# ESP32_CUSTOM.net
KiCad netlist of a schematic drawn in Altium Designer
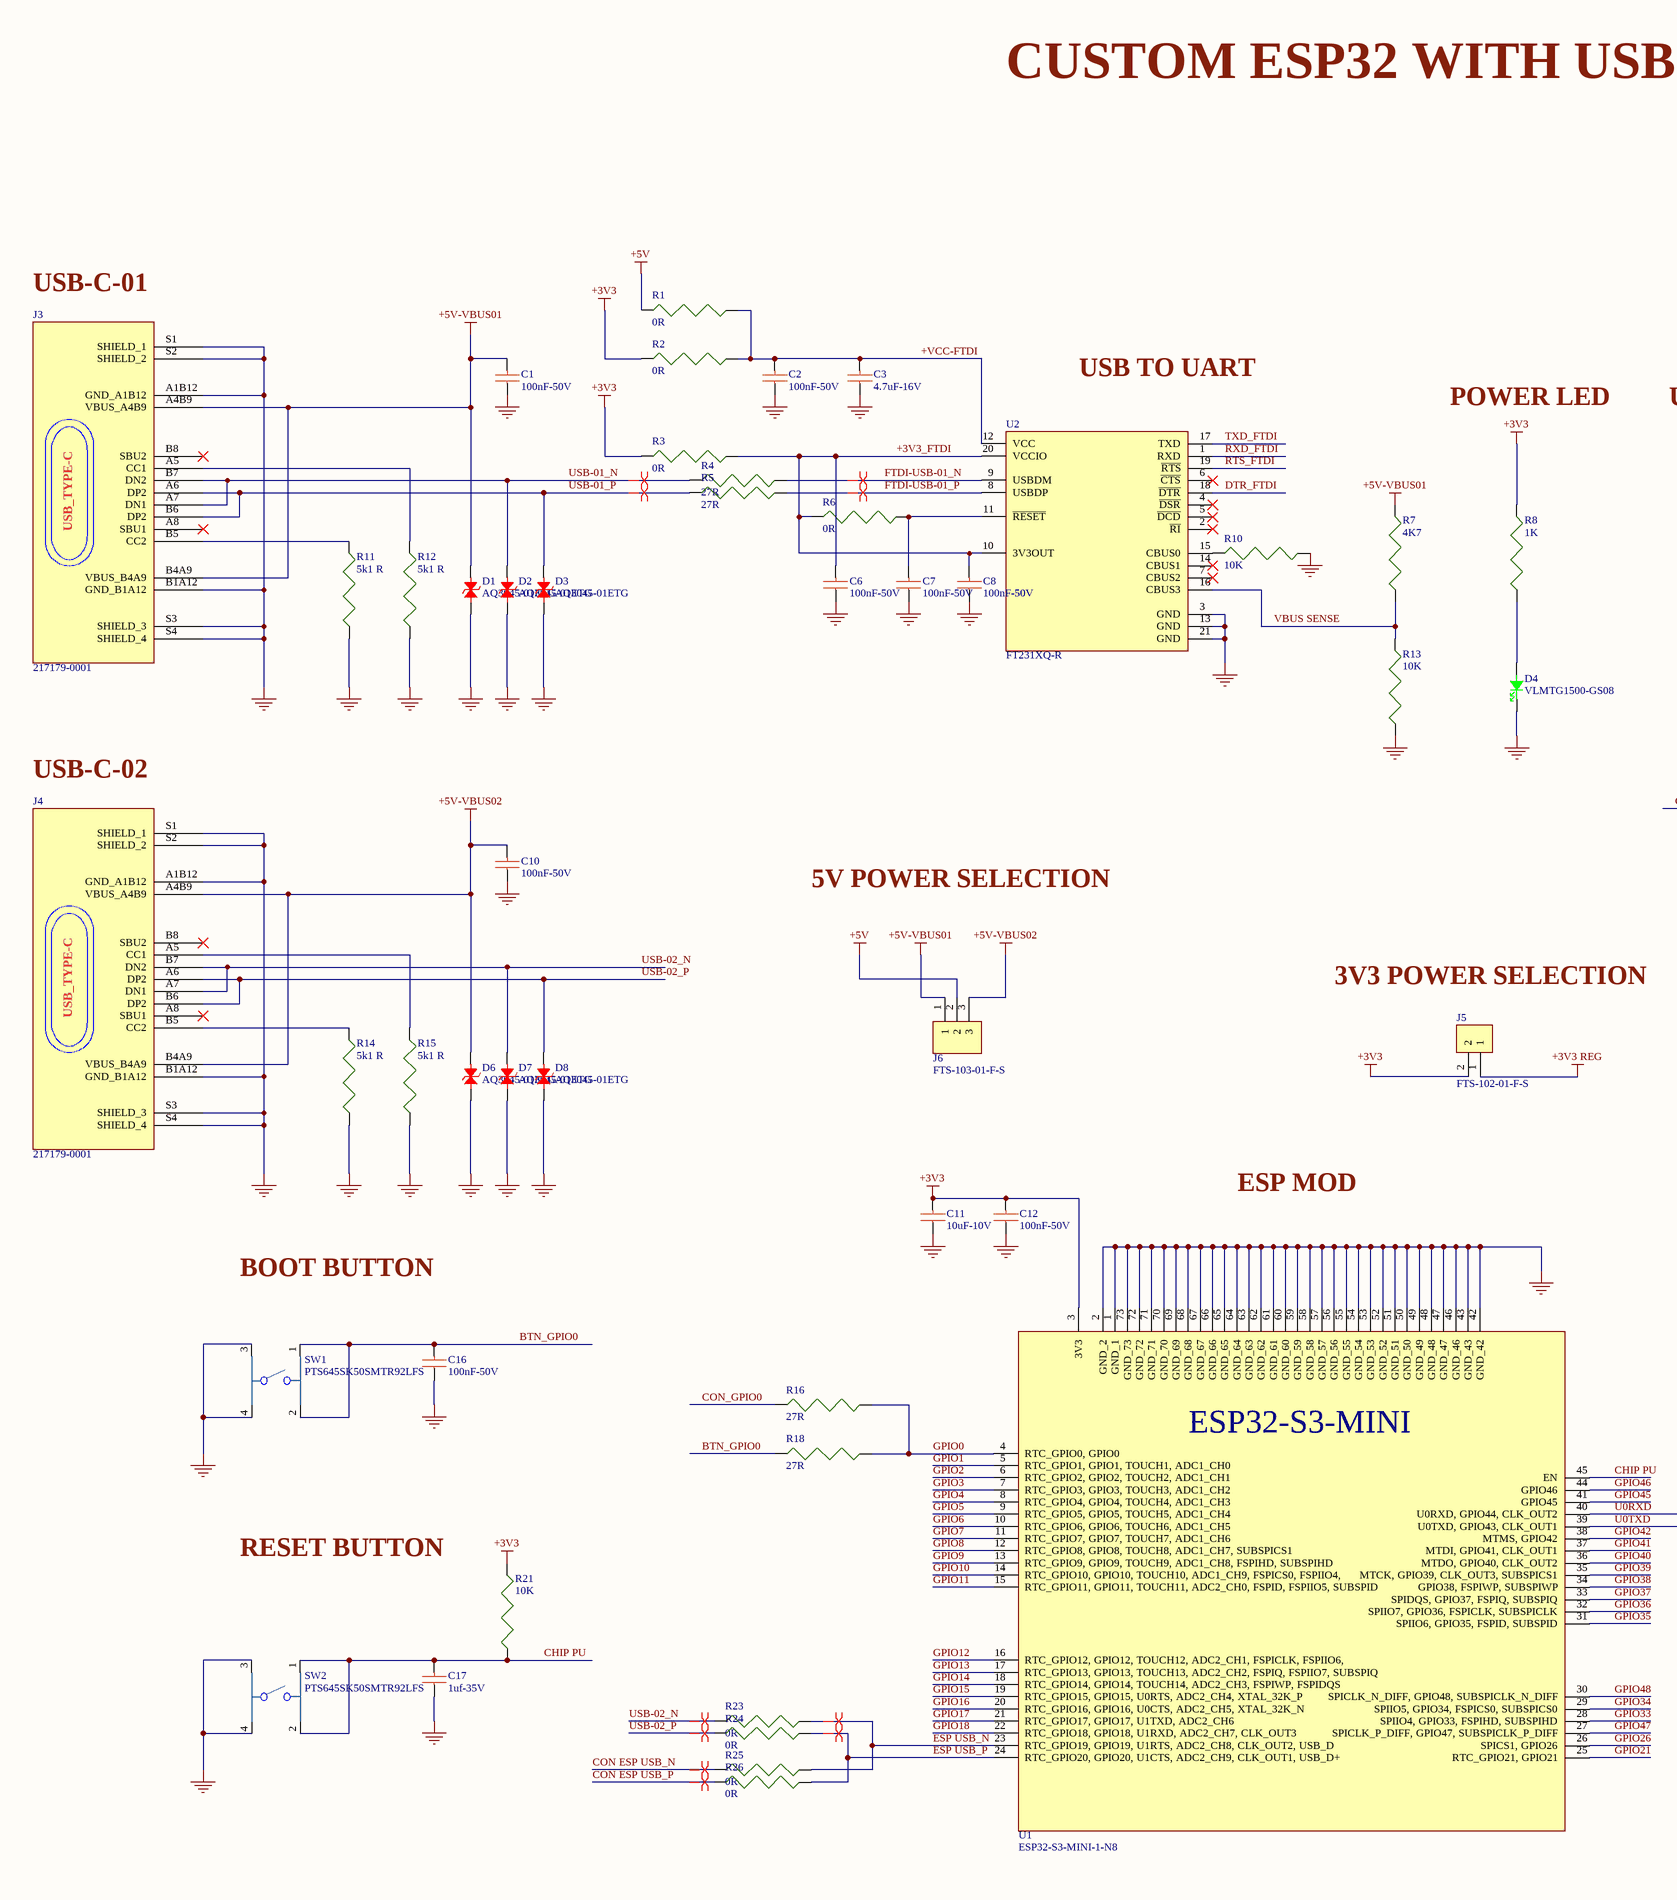
[diagram p0: ESP32_CUSTOM.SchDoc, left]
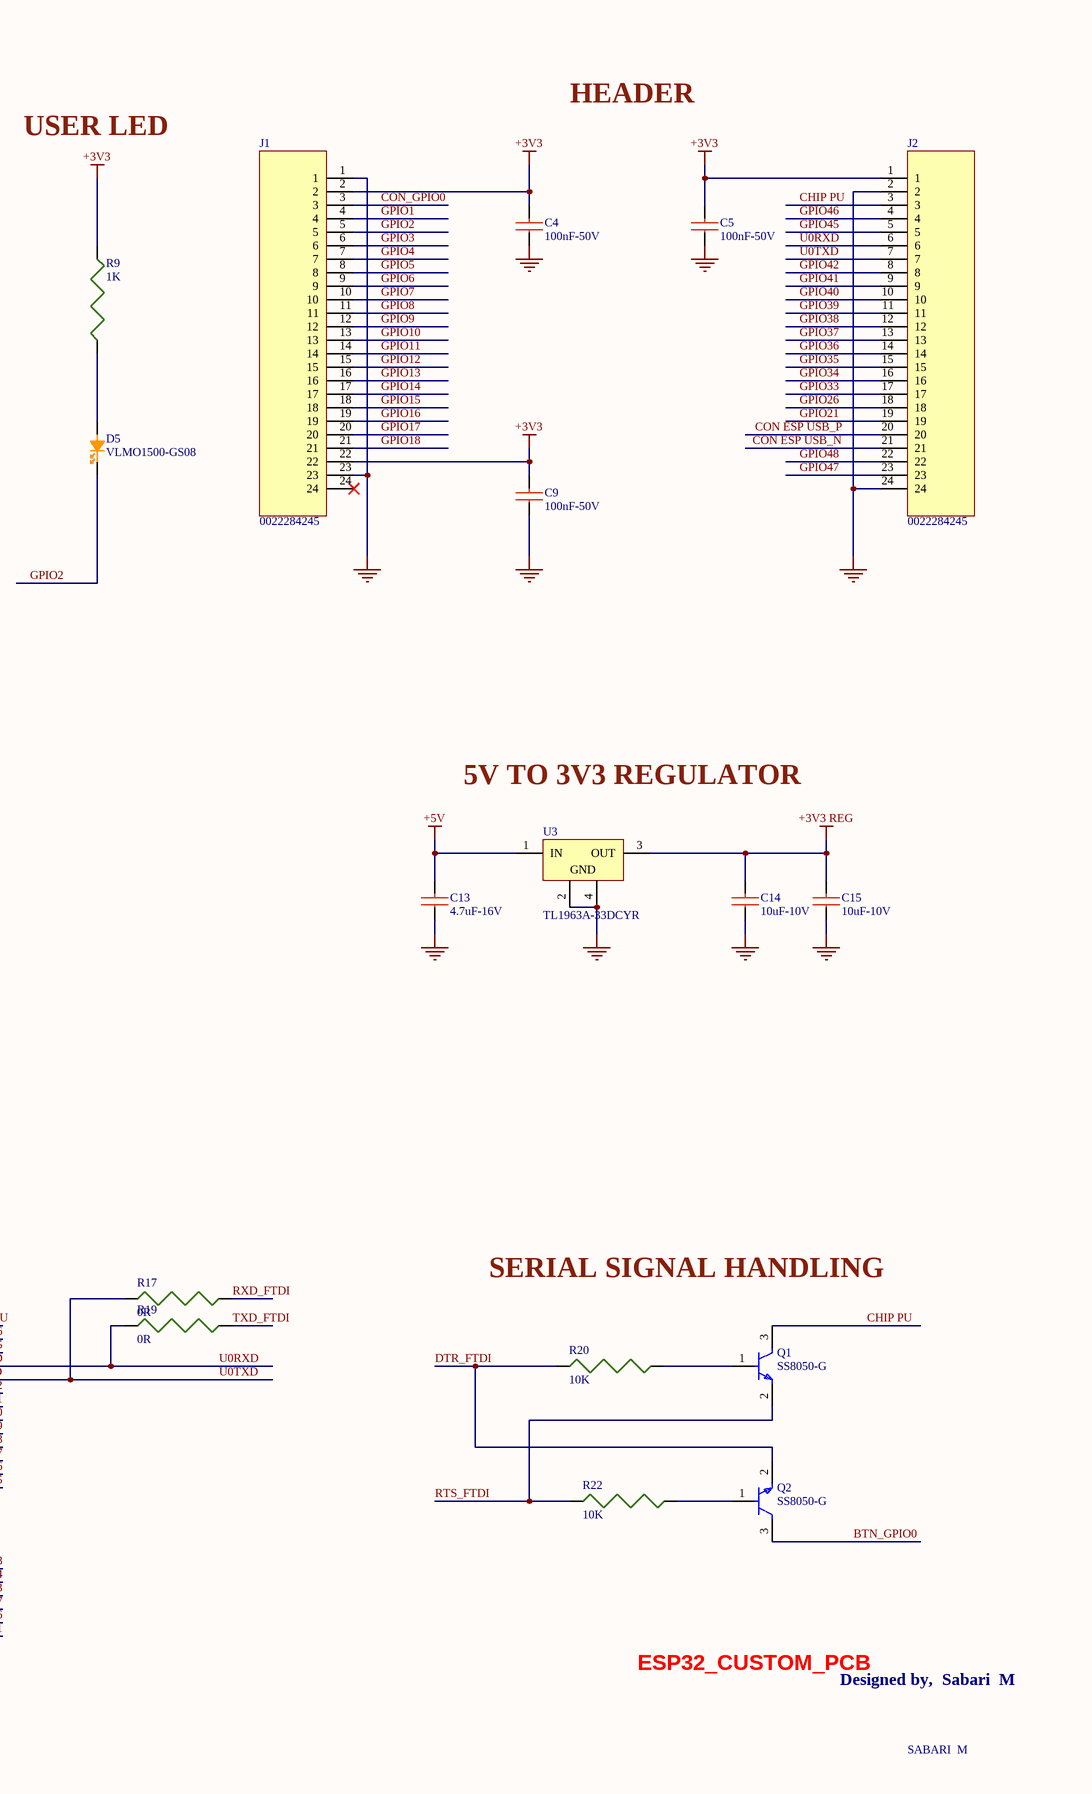
[diagram p1: ESP32_CUSTOM.SchDoc, right]

(export (version "E")
  (design (tool "Eeschema 10.0.6"))
  (components
    (comp (ref "C1")
      (value "100nF-50V")
      (footprint "FP-CL829-IPC_B")
      (description "CAP CER 0.1UF 50V X7R 0402")
      (fields
        (field (name "MANUFACTURER") "Samsung")
        (field (name "MANUFACTURER PART NUMBER") "CL05B104KB54PNC")
      )
      (libsource (lib "ESP32_CUSTOM") (part "CL05B104KB54PNC"))
    )
    (comp (ref "C2")
      (value "100nF-50V")
      (footprint "FP-CL829-IPC_B")
      (description "CAP CER 0.1UF 50V X7R 0402")
      (fields
        (field (name "MANUFACTURER") "Samsung")
        (field (name "MANUFACTURER PART NUMBER") "CL05B104KB54PNC")
      )
      (libsource (lib "ESP32_CUSTOM") (part "CL05B104KB54PNC"))
    )
    (comp (ref "C3")
      (value "4.7uF-16V")
      (footprint "FP-CL829-IPC_B")
      (description "CAP CER 4.7UF 16V X5R 0402")
      (fields
        (field (name "MANUFACTURER") "Samsung")
        (field (name "MANUFACTURER PART NUMBER") "CL05A475MO5NUNC")
      )
      (libsource (lib "ESP32_CUSTOM") (part "CL05A475MO5NUNC"))
    )
    (comp (ref "C4")
      (value "100nF-50V")
      (footprint "FP-CL829-IPC_B")
      (description "CAP CER 0.1UF 50V X7R 0402")
      (fields
        (field (name "MANUFACTURER") "Samsung")
        (field (name "MANUFACTURER PART NUMBER") "CL05B104KB54PNC")
      )
      (libsource (lib "ESP32_CUSTOM") (part "CL05B104KB54PNC"))
    )
    (comp (ref "C5")
      (value "100nF-50V")
      (footprint "FP-CL829-IPC_B")
      (description "CAP CER 0.1UF 50V X7R 0402")
      (fields
        (field (name "MANUFACTURER") "Samsung")
        (field (name "MANUFACTURER PART NUMBER") "CL05B104KB54PNC")
      )
      (libsource (lib "ESP32_CUSTOM") (part "CL05B104KB54PNC"))
    )
    (comp (ref "C6")
      (value "100nF-50V")
      (footprint "FP-CL829-IPC_B")
      (description "CAP CER 0.1UF 50V X7R 0402")
      (fields
        (field (name "MANUFACTURER") "Samsung")
        (field (name "MANUFACTURER PART NUMBER") "CL05B104KB54PNC")
      )
      (libsource (lib "ESP32_CUSTOM") (part "CL05B104KB54PNC"))
    )
    (comp (ref "C7")
      (value "100nF-50V")
      (footprint "FP-CL829-IPC_B")
      (description "CAP CER 0.1UF 50V X7R 0402")
      (fields
        (field (name "MANUFACTURER") "Samsung")
        (field (name "MANUFACTURER PART NUMBER") "CL05B104KB54PNC")
      )
      (libsource (lib "ESP32_CUSTOM") (part "CL05B104KB54PNC"))
    )
    (comp (ref "C8")
      (value "100nF-50V")
      (footprint "FP-CL829-IPC_B")
      (description "CAP CER 0.1UF 50V X7R 0402")
      (fields
        (field (name "MANUFACTURER") "Samsung")
        (field (name "MANUFACTURER PART NUMBER") "CL05B104KB54PNC")
      )
      (libsource (lib "ESP32_CUSTOM") (part "CL05B104KB54PNC"))
    )
    (comp (ref "C9")
      (value "100nF-50V")
      (footprint "FP-CL829-IPC_B")
      (description "CAP CER 0.1UF 50V X7R 0402")
      (fields
        (field (name "MANUFACTURER") "Samsung")
        (field (name "MANUFACTURER PART NUMBER") "CL05B104KB54PNC")
      )
      (libsource (lib "ESP32_CUSTOM") (part "CL05B104KB54PNC"))
    )
    (comp (ref "C10")
      (value "100nF-50V")
      (footprint "FP-CL829-IPC_B")
      (description "CAP CER 0.1UF 50V X7R 0402")
      (fields
        (field (name "MANUFACTURER") "Samsung")
        (field (name "MANUFACTURER PART NUMBER") "CL05B104KB54PNC")
      )
      (libsource (lib "ESP32_CUSTOM") (part "CL05B104KB54PNC"))
    )
    (comp (ref "C11")
      (value "10uF-10V")
      (footprint "FP-CL829-IPC_B")
      (description "CAP CER 10UF 10V X5R 0402")
      (fields
        (field (name "MANUFACTURER") "Samsung")
        (field (name "MANUFACTURER PART NUMBER") "CL05A106MP8NUB8")
      )
      (libsource (lib "ESP32_CUSTOM") (part "CL05A106MP8NUB8"))
    )
    (comp (ref "C12")
      (value "100nF-50V")
      (footprint "FP-CL829-IPC_B")
      (description "CAP CER 0.1UF 50V X7R 0402")
      (fields
        (field (name "MANUFACTURER") "Samsung")
        (field (name "MANUFACTURER PART NUMBER") "CL05B104KB54PNC")
      )
      (libsource (lib "ESP32_CUSTOM") (part "CL05B104KB54PNC"))
    )
    (comp (ref "C13")
      (value "4.7uF-16V")
      (footprint "FP-CL829-IPC_B")
      (description "CAP CER 4.7UF 16V X5R 0402")
      (fields
        (field (name "MANUFACTURER") "Samsung")
        (field (name "MANUFACTURER PART NUMBER") "CL05A475MO5NUNC")
      )
      (libsource (lib "ESP32_CUSTOM") (part "CL05A475MO5NUNC"))
    )
    (comp (ref "C14")
      (value "10uF-10V")
      (footprint "FP-CL829-IPC_B")
      (description "CAP CER 10UF 10V X5R 0402")
      (fields
        (field (name "MANUFACTURER") "Samsung")
        (field (name "MANUFACTURER PART NUMBER") "CL05A106MP8NUB8")
      )
      (libsource (lib "ESP32_CUSTOM") (part "CL05A106MP8NUB8"))
    )
    (comp (ref "C15")
      (value "10uF-10V")
      (footprint "FP-CL829-IPC_B")
      (description "CAP CER 10UF 10V X5R 0402")
      (fields
        (field (name "MANUFACTURER") "Samsung")
        (field (name "MANUFACTURER PART NUMBER") "CL05A106MP8NUB8")
      )
      (libsource (lib "ESP32_CUSTOM") (part "CL05A106MP8NUB8"))
    )
    (comp (ref "C16")
      (value "100nF-50V")
      (footprint "FP-CL829-IPC_B")
      (description "CAP CER 0.1UF 50V X7R 0402")
      (fields
        (field (name "MANUFACTURER") "Samsung")
        (field (name "MANUFACTURER PART NUMBER") "CL05B104KB54PNC")
      )
      (libsource (lib "ESP32_CUSTOM") (part "CL05B104KB54PNC"))
    )
    (comp (ref "C17")
      (value "1uf-35V")
      (footprint "FP-CL829-IPC_B")
      (description "CAP CER 1UF 35V X5R 0402")
      (fields
        (field (name "MANUFACTURER") "Samsung")
        (field (name "MANUFACTURER PART NUMBER") "CL05A105KL5NRNC")
      )
      (libsource (lib "ESP32_CUSTOM") (part "CL05A105KL5NRNC"))
    )
    (comp (ref "D1")
      (value "AQ3045-01ETG")
      (footprint "SOD882")
      (description "TVS DIODE 5.3VWM 12VC SOD882")
      (fields (field (name "MANUFACTURER") "Littelfuse") (field (name "LCSC PART NUMBER") "C3710326"))
      (libsource (lib "ESP32_CUSTOM") (part "AQ3045-01ETG"))
    )
    (comp (ref "D2")
      (value "AQ3045-01ETG")
      (footprint "SOD882")
      (description "TVS DIODE 5.3VWM 12VC SOD882")
      (fields (field (name "MANUFACTURER") "Littelfuse") (field (name "LCSC PART NUMBER") "C3710326"))
      (libsource (lib "ESP32_CUSTOM") (part "AQ3045-01ETG"))
    )
    (comp (ref "D3")
      (value "AQ3045-01ETG")
      (footprint "SOD882")
      (description "TVS DIODE 5.3VWM 12VC SOD882")
      (fields (field (name "MANUFACTURER") "Littelfuse") (field (name "LCSC PART NUMBER") "C3710326"))
      (libsource (lib "ESP32_CUSTOM") (part "AQ3045-01ETG"))
    )
    (comp (ref "D4")
      (value "VLMTG1500-GS08")
      (footprint "FP-APG1005CGC-T-MFG")
      (description "LED GREEN 0402 SMD")
      (fields (field (name "MANUFACTURER") "Vishay") (field (name "LCSC PART NUMBER") "C20346084"))
      (libsource (lib "ESP32_CUSTOM") (part "VLMTG1500-GS08"))
    )
    (comp (ref "D5")
      (value "VLMO1500-GS08")
      (footprint "FP-VLMO1500-GS08-MFG")
      (description "LED ORANGE 0402 SMD")
      (fields (field (name "MANUFACTURER") "Vishay") (field (name "LCSC PART NUMBER") "C3000857"))
      (libsource (lib "ESP32_CUSTOM") (part "VLMO1500-GS08"))
    )
    (comp (ref "D6")
      (value "AQ3045-01ETG")
      (footprint "SOD882")
      (description "TVS DIODE 5.3VWM 12VC SOD882")
      (fields (field (name "MANUFACTURER") "Littelfuse") (field (name "LCSC PART NUMBER") "C3710326"))
      (libsource (lib "ESP32_CUSTOM") (part "AQ3045-01ETG"))
    )
    (comp (ref "D7")
      (value "AQ3045-01ETG")
      (footprint "SOD882")
      (description "TVS DIODE 5.3VWM 12VC SOD882")
      (fields (field (name "MANUFACTURER") "Littelfuse") (field (name "LCSC PART NUMBER") "C3710326"))
      (libsource (lib "ESP32_CUSTOM") (part "AQ3045-01ETG"))
    )
    (comp (ref "D8")
      (value "AQ3045-01ETG")
      (footprint "SOD882")
      (description "TVS DIODE 5.3VWM 12VC SOD882")
      (fields (field (name "MANUFACTURER") "Littelfuse") (field (name "LCSC PART NUMBER") "C3710326"))
      (libsource (lib "ESP32_CUSTOM") (part "AQ3045-01ETG"))
    )
    (comp (ref "J1")
      (value "0022284245")
      (footprint "HDR_1X24_2.54MM")
      (description "CONN HEADER VERT 24POS 2.54MM")
      (fields (field (name "MANUFACTURER") "Molex") (field (name "LCSC PART NUMBER") "C7145888"))
      (libsource (lib "") (part "0022284245_1"))
    )
    (comp (ref "J2")
      (value "0022284245")
      (footprint "HDR_1X24_2.54MM")
      (description "CONN HEADER VERT 24POS 2.54MM")
      (fields (field (name "MANUFACTURER") "Molex") (field (name "LCSC PART NUMBER") "C7145888"))
      (libsource (lib "ESP32_CUSTOM") (part "0022284245"))
    )
    (comp (ref "J3")
      (value "217179-0001")
      (footprint "FP-2171790001-MFG")
      (description "CONN RCP USB2.0 TYP C 24P SMD RA")
      (fields (field (name "MANUFACTURER") "Molex") (field (name "LCSC PART NUMBER") "C3197684"))
      (libsource (lib "ESP32_CUSTOM") (part "217179-0001"))
    )
    (comp (ref "J4")
      (value "217179-0001")
      (footprint "FP-2171790001-MFG")
      (description "CONN RCP USB2.0 TYP C 24P SMD RA")
      (fields (field (name "MANUFACTURER") "Molex") (field (name "LCSC PART NUMBER") "C3197684"))
      (libsource (lib "ESP32_CUSTOM") (part "217179-0001"))
    )
    (comp (ref "J5")
      (value "FTS-102-01-F-S")
      (footprint "HDR_1X2_1.27MM")
      (description "CONN HEADER VERT 2POS 1.27MM")
      (fields (field (name "MANUFACTURER") "Samtec") (field (name "LCSC PART NUMBER") "C6045317"))
      (libsource (lib "ESP32_CUSTOM") (part "FTS-102-01-F-S"))
    )
    (comp (ref "J6")
      (value "FTS-103-01-F-S")
      (footprint "HDR_1X3_1.27MM")
      (description "CONN HEADER VERT 3POS 1.27MM")
      (fields (field (name "MANUFACTURER") "Samtec") (field (name "LCSC PART NUMBER") "C3333578"))
      (libsource (lib "ESP32_CUSTOM") (part "FTS-103-01-F-S"))
    )
    (comp (ref "Q1")
      (value "SS8050-G")
      (footprint "FP-SS8050-G-IPC_B")
      (description "TRANS NPN 25V 1.5A SOT23-3")
      (fields (field (name "MANUFACTURER") "Comchip") (field (name "LCSC PART NUMBER") "C164886"))
      (libsource (lib "ESP32_CUSTOM") (part "SS8050-G"))
    )
    (comp (ref "Q2")
      (value "SS8050-G")
      (footprint "FP-SS8050-G-IPC_B")
      (description "TRANS NPN 25V 1.5A SOT23-3")
      (fields (field (name "MANUFACTURER") "Comchip") (field (name "LCSC PART NUMBER") "C164886"))
      (libsource (lib "ESP32_CUSTOM") (part "SS8050-G"))
    )
    (comp (ref "R1")
      (value "0R")
      (footprint "FP-AC0402-IPC_A")
      (description "RES 0 OHM JUMPER 1/16W 0402")
      (fields
        (field (name "MANUFACTURER") "Yageo")
        (field (name "MANUFACTURER PART NUMBER") "RC0402JR-070RL")
      )
      (libsource (lib "ESP32_CUSTOM") (part "RC0402JR-070RL"))
    )
    (comp (ref "R2")
      (value "0R")
      (footprint "FP-AC0402-IPC_A")
      (description "RES 0 OHM JUMPER 1/16W 0402")
      (fields
        (field (name "MANUFACTURER") "Yageo")
        (field (name "MANUFACTURER PART NUMBER") "RC0402JR-070RL")
      )
      (libsource (lib "ESP32_CUSTOM") (part "RC0402JR-070RL"))
    )
    (comp (ref "R3")
      (value "0R")
      (footprint "FP-AC0402-IPC_A")
      (description "RES 0 OHM JUMPER 1/16W 0402")
      (fields
        (field (name "MANUFACTURER") "Yageo")
        (field (name "MANUFACTURER PART NUMBER") "RC0402JR-070RL")
      )
      (libsource (lib "ESP32_CUSTOM") (part "RC0402JR-070RL"))
    )
    (comp (ref "R4")
      (value "27R")
      (footprint "FP-AC0402-IPC_A")
      (description "RES 27 OHM 1% 1/16W 0402")
      (fields
        (field (name "MANUFACTURER") "Yageo")
        (field (name "MANUFACTURER PART NUMBER") "RC0402FR-0727RL")
      )
      (libsource (lib "ESP32_CUSTOM") (part "RC0402FR-0727RL"))
    )
    (comp (ref "R5")
      (value "27R")
      (footprint "FP-AC0402-IPC_A")
      (description "RES 27 OHM 1% 1/16W 0402")
      (fields
        (field (name "MANUFACTURER") "Yageo")
        (field (name "MANUFACTURER PART NUMBER") "RC0402FR-0727RL")
      )
      (libsource (lib "ESP32_CUSTOM") (part "RC0402FR-0727RL"))
    )
    (comp (ref "R6")
      (value "0R")
      (footprint "FP-AC0402-IPC_A")
      (description "RES 0 OHM JUMPER 1/16W 0402")
      (fields
        (field (name "MANUFACTURER") "Yageo")
        (field (name "MANUFACTURER PART NUMBER") "RC0402JR-070RL")
      )
      (libsource (lib "ESP32_CUSTOM") (part "RC0402JR-070RL"))
    )
    (comp (ref "R7")
      (value "4K7")
      (footprint "FP-AC0402-IPC_A")
      (description "RES 4.7K OHM 1% 1/16W 0402")
      (fields
        (field (name "MANUFACTURER") "Yageo")
        (field (name "MANUFACTURER PART NUMBER") "RC0402FR-074K7L")
      )
      (libsource (lib "ESP32_CUSTOM") (part "RC0402FR-074K7L"))
    )
    (comp (ref "R8")
      (value "1K")
      (footprint "FP-AC0402-IPC_A")
      (description "RES 1K OHM 1% 1/16W 0402")
      (fields
        (field (name "MANUFACTURER") "Yageo")
        (field (name "MANUFACTURER PART NUMBER") "RC0402FR-071KL")
      )
      (libsource (lib "ESP32_CUSTOM") (part "RC0402FR-071KL"))
    )
    (comp (ref "R9")
      (value "1K")
      (footprint "FP-AC0402-IPC_A")
      (description "RES 1K OHM 1% 1/16W 0402")
      (fields
        (field (name "MANUFACTURER") "Yageo")
        (field (name "MANUFACTURER PART NUMBER") "RC0402FR-071KL")
      )
      (libsource (lib "ESP32_CUSTOM") (part "RC0402FR-071KL"))
    )
    (comp (ref "R10")
      (value "10K")
      (footprint "FP-AC0402-IPC_A")
      (description "RES SMD 10K OHM 1% 1/16W 0402")
      (fields
        (field (name "MANUFACTURER") "Yageo")
        (field (name "MANUFACTURER PART NUMBER") "AC0402FR-0710KL")
      )
      (libsource (lib "ESP32_CUSTOM") (part "AC0402FR-0710KL"))
    )
    (comp (ref "R11")
      (value "5k1 R")
      (footprint "FP-AC0402-IPC_A")
      (description "RES SMD 5.1K OHM 1% 1/16W 0402")
      (fields
        (field (name "MANUFACTURER") "Yageo")
        (field (name "MANUFACTURER PART NUMBER") "AC0402FR-075K1L")
      )
      (libsource (lib "ESP32_CUSTOM") (part "AC0402FR-075K1L"))
    )
    (comp (ref "R12")
      (value "5k1 R")
      (footprint "FP-AC0402-IPC_A")
      (description "RES SMD 5.1K OHM 1% 1/16W 0402")
      (fields
        (field (name "MANUFACTURER") "Yageo")
        (field (name "MANUFACTURER PART NUMBER") "AC0402FR-075K1L")
      )
      (libsource (lib "ESP32_CUSTOM") (part "AC0402FR-075K1L"))
    )
    (comp (ref "R13")
      (value "10K")
      (footprint "FP-AC0402-IPC_A")
      (description "RES SMD 10K OHM 1% 1/16W 0402")
      (fields
        (field (name "MANUFACTURER") "Yageo")
        (field (name "MANUFACTURER PART NUMBER") "AC0402FR-0710KL")
      )
      (libsource (lib "ESP32_CUSTOM") (part "AC0402FR-0710KL"))
    )
    (comp (ref "R14")
      (value "5k1 R")
      (footprint "FP-AC0402-IPC_A")
      (description "RES SMD 5.1K OHM 1% 1/16W 0402")
      (fields
        (field (name "MANUFACTURER") "Yageo")
        (field (name "MANUFACTURER PART NUMBER") "AC0402FR-075K1L")
      )
      (libsource (lib "ESP32_CUSTOM") (part "AC0402FR-075K1L"))
    )
    (comp (ref "R15")
      (value "5k1 R")
      (footprint "FP-AC0402-IPC_A")
      (description "RES SMD 5.1K OHM 1% 1/16W 0402")
      (fields
        (field (name "MANUFACTURER") "Yageo")
        (field (name "MANUFACTURER PART NUMBER") "AC0402FR-075K1L")
      )
      (libsource (lib "ESP32_CUSTOM") (part "AC0402FR-075K1L"))
    )
    (comp (ref "R16")
      (value "27R")
      (footprint "FP-AC0402-IPC_A")
      (description "RES 27 OHM 1% 1/16W 0402")
      (fields
        (field (name "MANUFACTURER") "Yageo")
        (field (name "MANUFACTURER PART NUMBER") "RC0402FR-0727RL")
      )
      (libsource (lib "ESP32_CUSTOM") (part "RC0402FR-0727RL"))
    )
    (comp (ref "R17")
      (value "0R")
      (footprint "FP-AC0402-IPC_A")
      (description "RES 0 OHM JUMPER 1/16W 0402")
      (fields
        (field (name "MANUFACTURER") "Yageo")
        (field (name "MANUFACTURER PART NUMBER") "RC0402JR-070RL")
      )
      (libsource (lib "ESP32_CUSTOM") (part "RC0402JR-070RL"))
    )
    (comp (ref "R18")
      (value "27R")
      (footprint "FP-AC0402-IPC_A")
      (description "RES 27 OHM 1% 1/16W 0402")
      (fields
        (field (name "MANUFACTURER") "Yageo")
        (field (name "MANUFACTURER PART NUMBER") "RC0402FR-0727RL")
      )
      (libsource (lib "ESP32_CUSTOM") (part "RC0402FR-0727RL"))
    )
    (comp (ref "R19")
      (value "0R")
      (footprint "FP-AC0402-IPC_A")
      (description "RES 0 OHM JUMPER 1/16W 0402")
      (fields
        (field (name "MANUFACTURER") "Yageo")
        (field (name "MANUFACTURER PART NUMBER") "RC0402JR-070RL")
      )
      (libsource (lib "ESP32_CUSTOM") (part "RC0402JR-070RL"))
    )
    (comp (ref "R20")
      (value "10K")
      (footprint "FP-AC0402-IPC_A")
      (description "RES SMD 10K OHM 1% 1/16W 0402")
      (fields
        (field (name "MANUFACTURER") "Yageo")
        (field (name "MANUFACTURER PART NUMBER") "AC0402FR-0710KL")
      )
      (libsource (lib "ESP32_CUSTOM") (part "AC0402FR-0710KL"))
    )
    (comp (ref "R21")
      (value "10K")
      (footprint "FP-AC0402-IPC_A")
      (description "RES SMD 10K OHM 1% 1/16W 0402")
      (fields
        (field (name "MANUFACTURER") "Yageo")
        (field (name "MANUFACTURER PART NUMBER") "AC0402FR-0710KL")
      )
      (libsource (lib "ESP32_CUSTOM") (part "AC0402FR-0710KL"))
    )
    (comp (ref "R22")
      (value "10K")
      (footprint "FP-AC0402-IPC_A")
      (description "RES SMD 10K OHM 1% 1/16W 0402")
      (fields
        (field (name "MANUFACTURER") "Yageo")
        (field (name "MANUFACTURER PART NUMBER") "AC0402FR-0710KL")
      )
      (libsource (lib "ESP32_CUSTOM") (part "AC0402FR-0710KL"))
    )
    (comp (ref "R23")
      (value "0R")
      (footprint "FP-AC0402-IPC_A")
      (description "RES 0 OHM JUMPER 1/16W 0402")
      (fields
        (field (name "MANUFACTURER") "Yageo")
        (field (name "MANUFACTURER PART NUMBER") "RC0402JR-070RL")
      )
      (libsource (lib "ESP32_CUSTOM") (part "RC0402JR-070RL"))
    )
    (comp (ref "R24")
      (value "0R")
      (footprint "FP-AC0402-IPC_A")
      (description "RES 0 OHM JUMPER 1/16W 0402")
      (fields
        (field (name "MANUFACTURER") "Yageo")
        (field (name "MANUFACTURER PART NUMBER") "RC0402JR-070RL")
      )
      (libsource (lib "ESP32_CUSTOM") (part "RC0402JR-070RL"))
    )
    (comp (ref "R25")
      (value "0R")
      (footprint "FP-AC0402-IPC_A")
      (description "RES 0 OHM JUMPER 1/16W 0402")
      (fields
        (field (name "MANUFACTURER") "Yageo")
        (field (name "MANUFACTURER PART NUMBER") "RC0402JR-070RL")
      )
      (libsource (lib "ESP32_CUSTOM") (part "RC0402JR-070RL"))
    )
    (comp (ref "R26")
      (value "0R")
      (footprint "FP-AC0402-IPC_A")
      (description "RES 0 OHM JUMPER 1/16W 0402")
      (fields
        (field (name "MANUFACTURER") "Yageo")
        (field (name "MANUFACTURER PART NUMBER") "RC0402JR-070RL")
      )
      (libsource (lib "ESP32_CUSTOM") (part "RC0402JR-070RL"))
    )
    (comp (ref "SW1")
      (value "PTS645SK50SMTR92LFS")
      (footprint "FP-PTS645SM43SMTR92LFS-MFG")
      (description "SWITCH TACTILE SPST-NO 0.05A 12V")
      (fields (field (name "MANUFACTURER") "ITT C&K") (field (name "LCSC PART NUMBER") "C221872"))
      (libsource (lib "ESP32_CUSTOM") (part "PTS645SK50SMTR92LFS"))
    )
    (comp (ref "SW2")
      (value "PTS645SK50SMTR92LFS")
      (footprint "FP-PTS645SM43SMTR92LFS-MFG")
      (description "SWITCH TACTILE SPST-NO 0.05A 12V")
      (fields (field (name "MANUFACTURER") "ITT C&K") (field (name "LCSC PART NUMBER") "C221872"))
      (libsource (lib "ESP32_CUSTOM") (part "PTS645SK50SMTR92LFS"))
    )
    (comp (ref "U1")
      (value "ESP32-S3-MINI-1-N8")
      (footprint "XCVR_ESP32-S3-MINI-1-N8")
      (description "SMD module, ESP32-S3FN8, 8 MB SPI flash, PCB antenna")
      (fields (field (name "MANUFACTURER") "Espressif Systems") (field (name "LCSC PART NUMBER") "C2913206"))
      (libsource (lib "ESP32_CUSTOM") (part "ESP32-S3-MINI-1-N8"))
    )
    (comp (ref "U2")
      (value "FT231XQ-R")
      (footprint "FP-QFN-20-IPC_B")
      (description "IC USB SERIAL FULL UART 20QFN")
      (fields (field (name "MANUFACTURER") "FTDI") (field (name "LCSC PART NUMBER") "C132159"))
      (libsource (lib "ESP32_CUSTOM") (part "FT231XQ-R"))
    )
    (comp (ref "U3")
      (value "TL1963A-33DCYR")
      (footprint "DCY0004A_N")
      (description "IC REG LINEAR 3.3V 1.5A SOT223-4")
      (fields (field (name "MANUFACTURER") "Texas Instruments") (field (name "LCSC PART NUMBER") "C181262"))
      (libsource (lib "ESP32_CUSTOM") (part "TL1963A-33DCYR"))
    )
  )
  (nets
    (net (code "1") (name "+3V3") (class "Default")
      (node (ref "C11") (pin "2") (pinfunction "2_2") (pintype "passive"))
      (node (ref "C12") (pin "2") (pinfunction "2_2") (pintype "passive"))
      (node (ref "C4") (pin "2") (pinfunction "2_2") (pintype "passive"))
      (node (ref "C5") (pin "2") (pinfunction "2_2") (pintype "passive"))
      (node (ref "C9") (pin "2") (pinfunction "2_2") (pintype "passive"))
      (node (ref "J1") (pin "2") (pinfunction "2_2") (pintype "passive"))
      (node (ref "J1") (pin "22") (pinfunction "22_22") (pintype "passive"))
      (node (ref "J2") (pin "1") (pinfunction "1_1") (pintype "passive"))
      (node (ref "J5") (pin "2") (pinfunction "2_2") (pintype "passive"))
      (node (ref "R2") (pin "1") (pinfunction "1_1") (pintype "passive"))
      (node (ref "R21") (pin "1") (pinfunction "1_1") (pintype "passive"))
      (node (ref "R3") (pin "1") (pinfunction "1_1") (pintype "passive"))
      (node (ref "R8") (pin "2") (pinfunction "2_2") (pintype "passive"))
      (node (ref "R9") (pin "2") (pinfunction "2_2") (pintype "passive"))
      (node (ref "U1") (pin "3") (pinfunction "3V3_3") (pintype "passive"))
    )
    (net (code "2") (name "+3V3 REG") (class "Default")
      (node (ref "C14") (pin "2") (pinfunction "2_2") (pintype "passive"))
      (node (ref "C15") (pin "2") (pinfunction "2_2") (pintype "passive"))
      (node (ref "J5") (pin "1") (pinfunction "1_1") (pintype "passive"))
      (node (ref "U3") (pin "3") (pinfunction "OUT_3") (pintype "power_in"))
    )
    (net (code "3") (name "+5V") (class "Default")
      (node (ref "C13") (pin "2") (pinfunction "2_2") (pintype "passive"))
      (node (ref "J6") (pin "2") (pinfunction "2_2") (pintype "passive"))
      (node (ref "R1") (pin "1") (pinfunction "1_1") (pintype "passive"))
      (node (ref "U3") (pin "1") (pinfunction "IN_1") (pintype "power_in"))
    )
    (net (code "4") (name "+5V-VBUS01") (class "Default")
      (node (ref "C1") (pin "2") (pinfunction "2_2") (pintype "passive"))
      (node (ref "D1") (pin "1") (pinfunction "1_1") (pintype "passive"))
      (node (ref "J3") (pin "A4B9") (pinfunction "VBUS_A4B9_A4B9") (pintype "passive"))
      (node (ref "J3") (pin "B4A9") (pinfunction "VBUS_B4A9_B4A9") (pintype "passive"))
      (node (ref "J6") (pin "1") (pinfunction "1_1") (pintype "passive"))
      (node (ref "R7") (pin "2") (pinfunction "2_2") (pintype "passive"))
    )
    (net (code "5") (name "+5V-VBUS02") (class "Default")
      (node (ref "C10") (pin "2") (pinfunction "2_2") (pintype "passive"))
      (node (ref "D6") (pin "1") (pinfunction "1_1") (pintype "passive"))
      (node (ref "J4") (pin "A4B9") (pinfunction "VBUS_A4B9_A4B9") (pintype "passive"))
      (node (ref "J4") (pin "B4A9") (pinfunction "VBUS_B4A9_B4A9") (pintype "passive"))
      (node (ref "J6") (pin "3") (pinfunction "3_3") (pintype "passive"))
    )
    (net (code "6") (name "/+3V3_FTDI") (class "Default")
      (node (ref "C6") (pin "2") (pinfunction "2_2") (pintype "passive"))
      (node (ref "C8") (pin "2") (pinfunction "2_2") (pintype "passive"))
      (node (ref "R3") (pin "2") (pinfunction "2_2") (pintype "passive"))
      (node (ref "R6") (pin "1") (pinfunction "1_1") (pintype "passive"))
      (node (ref "U2") (pin "10") (pinfunction "3V3OUT_10") (pintype "passive"))
      (node (ref "U2") (pin "20") (pinfunction "VCCIO_20") (pintype "passive"))
    )
    (net (code "7") (name "/+VCC-FTDI") (class "Default")
      (node (ref "C2") (pin "2") (pinfunction "2_2") (pintype "passive"))
      (node (ref "C3") (pin "2") (pinfunction "2_2") (pintype "passive"))
      (node (ref "R1") (pin "2") (pinfunction "2_2") (pintype "passive"))
      (node (ref "R2") (pin "2") (pinfunction "2_2") (pintype "passive"))
      (node (ref "U2") (pin "12") (pinfunction "VCC_12") (pintype "passive"))
    )
    (net (code "8") (name "/BTN_GPIO0") (class "Default")
      (node (ref "C16") (pin "2") (pinfunction "2_2") (pintype "passive"))
      (node (ref "Q2") (pin "3") (pinfunction "C_3") (pintype "passive"))
      (node (ref "R18") (pin "1") (pinfunction "1_1") (pintype "passive"))
      (node (ref "SW1") (pin "1") (pinfunction "1_1") (pintype "passive"))
      (node (ref "SW1") (pin "2") (pinfunction "2_2") (pintype "passive"))
    )
    (net (code "9") (name "/CHIP PU") (class "Default")
      (node (ref "C17") (pin "2") (pinfunction "2_2") (pintype "passive"))
      (node (ref "J2") (pin "3") (pinfunction "3_3") (pintype "passive"))
      (node (ref "Q1") (pin "3") (pinfunction "C_3") (pintype "passive"))
      (node (ref "R21") (pin "2") (pinfunction "2_2") (pintype "passive"))
      (node (ref "SW2") (pin "1") (pinfunction "1_1") (pintype "passive"))
      (node (ref "SW2") (pin "2") (pinfunction "2_2") (pintype "passive"))
      (node (ref "U1") (pin "45") (pinfunction "EN_45") (pintype "passive"))
    )
    (net (code "10") (name "/CON ESP USB_N") (class "Default")
      (node (ref "J2") (pin "21") (pinfunction "21_21") (pintype "passive"))
      (node (ref "R25") (pin "1") (pinfunction "1_1") (pintype "passive"))
    )
    (net (code "11") (name "/CON ESP USB_P") (class "Default")
      (node (ref "J2") (pin "20") (pinfunction "20_20") (pintype "passive"))
      (node (ref "R26") (pin "1") (pinfunction "1_1") (pintype "passive"))
    )
    (net (code "12") (name "/CON_GPIO0") (class "Default")
      (node (ref "J1") (pin "3") (pinfunction "3_3") (pintype "passive"))
      (node (ref "R16") (pin "1") (pinfunction "1_1") (pintype "passive"))
    )
    (net (code "13") (name "/DTR_FTDI") (class "Default")
      (node (ref "Q2") (pin "2") (pinfunction "E_2") (pintype "passive"))
      (node (ref "R20") (pin "2") (pinfunction "2_2") (pintype "passive"))
      (node (ref "U2") (pin "18") (pinfunction "~{DTR}_18") (pintype "passive"))
    )
    (net (code "14") (name "/ESP USB_N") (class "Default")
      (node (ref "R23") (pin "2") (pinfunction "2_2") (pintype "passive"))
      (node (ref "R25") (pin "2") (pinfunction "2_2") (pintype "passive"))
      (node (ref "U1") (pin "23") (pinfunction "RTC_GPIO19,_GPIO19,_U1RTS,_ADC2_CH8,_CLK_OUT2,_USB_D_23") (pintype "passive"))
    )
    (net (code "15") (name "/ESP USB_P") (class "Default")
      (node (ref "R24") (pin "2") (pinfunction "2_2") (pintype "passive"))
      (node (ref "R26") (pin "2") (pinfunction "2_2") (pintype "passive"))
      (node (ref "U1") (pin "24") (pinfunction "RTC_GPIO20,_GPIO20,_U1CTS,_ADC2_CH9,_CLK_OUT1,_USB_D+_24") (pintype "passive"))
    )
    (net (code "16") (name "/FTDI-USB-01_N") (class "Default")
      (node (ref "R4") (pin "2") (pinfunction "2_2") (pintype "passive"))
      (node (ref "U2") (pin "9") (pinfunction "USBDM_9") (pintype "passive"))
    )
    (net (code "17") (name "/FTDI-USB-01_P") (class "Default")
      (node (ref "R5") (pin "2") (pinfunction "2_2") (pintype "passive"))
      (node (ref "U2") (pin "8") (pinfunction "USBDP_8") (pintype "passive"))
    )
    (net (code "18") (name "/GPIO0") (class "Default")
      (node (ref "R16") (pin "2") (pinfunction "2_2") (pintype "passive"))
      (node (ref "R18") (pin "2") (pinfunction "2_2") (pintype "passive"))
      (node (ref "U1") (pin "4") (pinfunction "RTC_GPIO0,_GPIO0_4") (pintype "passive"))
    )
    (net (code "19") (name "/GPIO1") (class "Default")
      (node (ref "J1") (pin "4") (pinfunction "4_4") (pintype "passive"))
      (node (ref "U1") (pin "5") (pinfunction "RTC_GPIO1,_GPIO1,_TOUCH1,_ADC1_CH0_5") (pintype "passive"))
    )
    (net (code "20") (name "/GPIO2") (class "Default")
      (node (ref "D5") (pin "1") (pinfunction "1_1") (pintype "passive"))
      (node (ref "J1") (pin "5") (pinfunction "5_5") (pintype "passive"))
      (node (ref "U1") (pin "6") (pinfunction "RTC_GPIO2,_GPIO2,_TOUCH2,_ADC1_CH1_6") (pintype "passive"))
    )
    (net (code "21") (name "/GPIO3") (class "Default")
      (node (ref "J1") (pin "6") (pinfunction "6_6") (pintype "passive"))
      (node (ref "U1") (pin "7") (pinfunction "RTC_GPIO3,_GPIO3,_TOUCH3,_ADC1_CH2_7") (pintype "passive"))
    )
    (net (code "22") (name "/GPIO4") (class "Default")
      (node (ref "J1") (pin "7") (pinfunction "7_7") (pintype "passive"))
      (node (ref "U1") (pin "8") (pinfunction "RTC_GPIO4,_GPIO4,_TOUCH4,_ADC1_CH3_8") (pintype "passive"))
    )
    (net (code "23") (name "/GPIO5") (class "Default")
      (node (ref "J1") (pin "8") (pinfunction "8_8") (pintype "passive"))
      (node (ref "U1") (pin "9") (pinfunction "RTC_GPIO5,_GPIO5,_TOUCH5,_ADC1_CH4_9") (pintype "passive"))
    )
    (net (code "24") (name "/GPIO6") (class "Default")
      (node (ref "J1") (pin "9") (pinfunction "9_9") (pintype "passive"))
      (node (ref "U1") (pin "10") (pinfunction "RTC_GPIO6,_GPIO6,_TOUCH6,_ADC1_CH5_10") (pintype "passive"))
    )
    (net (code "25") (name "/GPIO7") (class "Default")
      (node (ref "J1") (pin "10") (pinfunction "10_10") (pintype "passive"))
      (node (ref "U1") (pin "11") (pinfunction "RTC_GPIO7,_GPIO7,_TOUCH7,_ADC1_CH6_11") (pintype "passive"))
    )
    (net (code "26") (name "/GPIO8") (class "Default")
      (node (ref "J1") (pin "11") (pinfunction "11_11") (pintype "passive"))
      (node (ref "U1") (pin "12") (pinfunction "RTC_GPIO8,_GPIO8,_TOUCH8,_ADC1_CH7,_SUBSPICS1_12") (pintype "passive"))
    )
    (net (code "27") (name "/GPIO9") (class "Default")
      (node (ref "J1") (pin "12") (pinfunction "12_12") (pintype "passive"))
      (node (ref "U1") (pin "13") (pinfunction "RTC_GPIO9,_GPIO9,_TOUCH9,_ADC1_CH8,_FSPIHD,_SUBSPIHD_13") (pintype "passive"))
    )
    (net (code "28") (name "/GPIO10") (class "Default")
      (node (ref "J1") (pin "13") (pinfunction "13_13") (pintype "passive"))
      (node (ref "U1") (pin "14") (pinfunction "RTC_GPIO10,_GPIO10,_TOUCH10,_ADC1_CH9,_FSPICS0,_FSPIIO4,_14") (pintype "passive"))
    )
    (net (code "29") (name "/GPIO11") (class "Default")
      (node (ref "J1") (pin "14") (pinfunction "14_14") (pintype "passive"))
      (node (ref "U1") (pin "15") (pinfunction "RTC_GPIO11,_GPIO11,_TOUCH11,_ADC2_CH0,_FSPID,_FSPIIO5,_SUBSPID_15") (pintype "passive"))
    )
    (net (code "30") (name "/GPIO12") (class "Default")
      (node (ref "J1") (pin "15") (pinfunction "15_15") (pintype "passive"))
      (node (ref "U1") (pin "16") (pinfunction "RTC_GPIO12,_GPIO12,_TOUCH12,_ADC2_CH1,_FSPICLK,_FSPIIO6,_16") (pintype "passive"))
    )
    (net (code "31") (name "/GPIO13") (class "Default")
      (node (ref "J1") (pin "16") (pinfunction "16_16") (pintype "passive"))
      (node (ref "U1") (pin "17") (pinfunction "RTC_GPIO13,_GPIO13,_TOUCH13,_ADC2_CH2,_FSPIQ,_FSPIIO7,_SUBSPIQ_17") (pintype "passive"))
    )
    (net (code "32") (name "/GPIO14") (class "Default")
      (node (ref "J1") (pin "17") (pinfunction "17_17") (pintype "passive"))
      (node (ref "U1") (pin "18") (pinfunction "RTC_GPIO14,_GPIO14,_TOUCH14,_ADC2_CH3,_FSPIWP,_FSPIDQS_18") (pintype "passive"))
    )
    (net (code "33") (name "/GPIO15") (class "Default")
      (node (ref "J1") (pin "18") (pinfunction "18_18") (pintype "passive"))
      (node (ref "U1") (pin "19") (pinfunction "RTC_GPIO15,_GPIO15,_U0RTS,_ADC2_CH4,_XTAL_32K_P_19") (pintype "passive"))
    )
    (net (code "34") (name "/GPIO16") (class "Default")
      (node (ref "J1") (pin "19") (pinfunction "19_19") (pintype "passive"))
      (node (ref "U1") (pin "20") (pinfunction "RTC_GPIO16,_GPIO16,_U0CTS,_ADC2_CH5,_XTAL_32K_N_20") (pintype "passive"))
    )
    (net (code "35") (name "/GPIO17") (class "Default")
      (node (ref "J1") (pin "20") (pinfunction "20_20") (pintype "passive"))
      (node (ref "U1") (pin "21") (pinfunction "RTC_GPIO17,_GPIO17,_U1TXD,_ADC2_CH6_21") (pintype "passive"))
    )
    (net (code "36") (name "/GPIO18") (class "Default")
      (node (ref "J1") (pin "21") (pinfunction "21_21") (pintype "passive"))
      (node (ref "U1") (pin "22") (pinfunction "RTC_GPIO18,_GPIO18,_U1RXD,_ADC2_CH7,_CLK_OUT3_22") (pintype "passive"))
    )
    (net (code "37") (name "/GPIO21") (class "Default")
      (node (ref "J2") (pin "19") (pinfunction "19_19") (pintype "passive"))
      (node (ref "U1") (pin "25") (pinfunction "RTC_GPIO21,_GPIO21_25") (pintype "passive"))
    )
    (net (code "38") (name "/GPIO26") (class "Default")
      (node (ref "J2") (pin "18") (pinfunction "18_18") (pintype "passive"))
      (node (ref "U1") (pin "26") (pinfunction "SPICS1,_GPIO26_26") (pintype "passive"))
    )
    (net (code "39") (name "/GPIO33") (class "Default")
      (node (ref "J2") (pin "17") (pinfunction "17_17") (pintype "passive"))
      (node (ref "U1") (pin "28") (pinfunction "SPIIO4,_GPIO33,_FSPIHD,_SUBSPIHD_28") (pintype "passive"))
    )
    (net (code "40") (name "/GPIO34") (class "Default")
      (node (ref "J2") (pin "16") (pinfunction "16_16") (pintype "passive"))
      (node (ref "U1") (pin "29") (pinfunction "SPIIO5,_GPIO34,_FSPICS0,_SUBSPICS0_29") (pintype "passive"))
    )
    (net (code "41") (name "/GPIO35") (class "Default")
      (node (ref "J2") (pin "15") (pinfunction "15_15") (pintype "passive"))
      (node (ref "U1") (pin "31") (pinfunction "SPIIO6,_GPIO35,_FSPID,_SUBSPID_31") (pintype "passive"))
    )
    (net (code "42") (name "/GPIO36") (class "Default")
      (node (ref "J2") (pin "14") (pinfunction "14_14") (pintype "passive"))
      (node (ref "U1") (pin "32") (pinfunction "SPIIO7,_GPIO36,_FSPICLK,_SUBSPICLK_32") (pintype "passive"))
    )
    (net (code "43") (name "/GPIO37") (class "Default")
      (node (ref "J2") (pin "13") (pinfunction "13_13") (pintype "passive"))
      (node (ref "U1") (pin "33") (pinfunction "SPIDQS,_GPIO37,_FSPIQ,_SUBSPIQ_33") (pintype "passive"))
    )
    (net (code "44") (name "/GPIO38") (class "Default")
      (node (ref "J2") (pin "12") (pinfunction "12_12") (pintype "passive"))
      (node (ref "U1") (pin "34") (pinfunction "GPIO38,_FSPIWP,_SUBSPIWP_34") (pintype "passive"))
    )
    (net (code "45") (name "/GPIO39") (class "Default")
      (node (ref "J2") (pin "11") (pinfunction "11_11") (pintype "passive"))
      (node (ref "U1") (pin "35") (pinfunction "MTCK,_GPIO39,_CLK_OUT3,_SUBSPICS1_35") (pintype "passive"))
    )
    (net (code "46") (name "/GPIO40") (class "Default")
      (node (ref "J2") (pin "10") (pinfunction "10_10") (pintype "passive"))
      (node (ref "U1") (pin "36") (pinfunction "MTDO,_GPIO40,_CLK_OUT2_36") (pintype "passive"))
    )
    (net (code "47") (name "/GPIO41") (class "Default")
      (node (ref "J2") (pin "9") (pinfunction "9_9") (pintype "passive"))
      (node (ref "U1") (pin "37") (pinfunction "MTDI,_GPIO41,_CLK_OUT1_37") (pintype "passive"))
    )
    (net (code "48") (name "/GPIO42") (class "Default")
      (node (ref "J2") (pin "8") (pinfunction "8_8") (pintype "passive"))
      (node (ref "U1") (pin "38") (pinfunction "MTMS,_GPIO42_38") (pintype "passive"))
    )
    (net (code "49") (name "/GPIO45") (class "Default")
      (node (ref "J2") (pin "5") (pinfunction "5_5") (pintype "passive"))
      (node (ref "U1") (pin "41") (pinfunction "GPIO45_41") (pintype "passive"))
    )
    (net (code "50") (name "/GPIO46") (class "Default")
      (node (ref "J2") (pin "4") (pinfunction "4_4") (pintype "passive"))
      (node (ref "U1") (pin "44") (pinfunction "GPIO46_44") (pintype "passive"))
    )
    (net (code "51") (name "/GPIO47") (class "Default")
      (node (ref "J2") (pin "23") (pinfunction "23_23") (pintype "passive"))
      (node (ref "U1") (pin "27") (pinfunction "SPICLK_P_DIFF,_GPIO47,_SUBSPICLK_P_DIFF_27") (pintype "passive"))
    )
    (net (code "52") (name "/GPIO48") (class "Default")
      (node (ref "J2") (pin "22") (pinfunction "22_22") (pintype "passive"))
      (node (ref "U1") (pin "30") (pinfunction "SPICLK_N_DIFF,_GPIO48,_SUBSPICLK_N_DIFF_30") (pintype "passive"))
    )
    (net (code "53") (name "/RTS_FTDI") (class "Default")
      (node (ref "Q1") (pin "2") (pinfunction "E_2") (pintype "passive"))
      (node (ref "R22") (pin "2") (pinfunction "2_2") (pintype "passive"))
      (node (ref "U2") (pin "19") (pinfunction "~{RTS}_19") (pintype "passive"))
    )
    (net (code "54") (name "/RXD_FTDI") (class "Default")
      (node (ref "R17") (pin "2") (pinfunction "2_2") (pintype "passive"))
      (node (ref "U2") (pin "1") (pinfunction "RXD_1") (pintype "passive"))
    )
    (net (code "55") (name "/TXD_FTDI") (class "Default")
      (node (ref "R19") (pin "2") (pinfunction "2_2") (pintype "passive"))
      (node (ref "U2") (pin "17") (pinfunction "TXD_17") (pintype "passive"))
    )
    (net (code "56") (name "/U0RXD") (class "Default")
      (node (ref "J2") (pin "6") (pinfunction "6_6") (pintype "passive"))
      (node (ref "R19") (pin "1") (pinfunction "1_1") (pintype "passive"))
      (node (ref "U1") (pin "40") (pinfunction "U0RXD,_GPIO44,_CLK_OUT2_40") (pintype "passive"))
    )
    (net (code "57") (name "/U0TXD") (class "Default")
      (node (ref "J2") (pin "7") (pinfunction "7_7") (pintype "passive"))
      (node (ref "R17") (pin "1") (pinfunction "1_1") (pintype "passive"))
      (node (ref "U1") (pin "39") (pinfunction "U0TXD,_GPIO43,_CLK_OUT1_39") (pintype "passive"))
    )
    (net (code "58") (name "/USB-01_N") (class "Default")
      (node (ref "D2") (pin "1") (pinfunction "1_1") (pintype "passive"))
      (node (ref "J3") (pin "A7") (pinfunction "DN1_A7") (pintype "passive"))
      (node (ref "J3") (pin "B7") (pinfunction "DN2_B7") (pintype "passive"))
      (node (ref "R4") (pin "1") (pinfunction "1_1") (pintype "passive"))
    )
    (net (code "59") (name "/USB-01_P") (class "Default")
      (node (ref "D3") (pin "1") (pinfunction "1_1") (pintype "passive"))
      (node (ref "J3") (pin "A6") (pinfunction "DP2_A6") (pintype "passive"))
      (node (ref "J3") (pin "B6") (pinfunction "DP2_B6") (pintype "passive"))
      (node (ref "R5") (pin "1") (pinfunction "1_1") (pintype "passive"))
    )
    (net (code "60") (name "/USB-02_N") (class "Default")
      (node (ref "D7") (pin "1") (pinfunction "1_1") (pintype "passive"))
      (node (ref "J4") (pin "A7") (pinfunction "DN1_A7") (pintype "passive"))
      (node (ref "J4") (pin "B7") (pinfunction "DN2_B7") (pintype "passive"))
      (node (ref "R23") (pin "1") (pinfunction "1_1") (pintype "passive"))
    )
    (net (code "61") (name "/USB-02_P") (class "Default")
      (node (ref "D8") (pin "1") (pinfunction "1_1") (pintype "passive"))
      (node (ref "J4") (pin "A6") (pinfunction "DP2_A6") (pintype "passive"))
      (node (ref "J4") (pin "B6") (pinfunction "DP2_B6") (pintype "passive"))
      (node (ref "R24") (pin "1") (pinfunction "1_1") (pintype "passive"))
    )
    (net (code "62") (name "/VBUS SENSE") (class "Default")
      (node (ref "R13") (pin "2") (pinfunction "2_2") (pintype "passive"))
      (node (ref "R7") (pin "1") (pinfunction "1_1") (pintype "passive"))
      (node (ref "U2") (pin "16") (pinfunction "CBUS3_16") (pintype "passive"))
    )
    (net (code "63") (name "GND") (class "Default")
      (node (ref "C1") (pin "1") (pinfunction "1_1") (pintype "passive"))
      (node (ref "C10") (pin "1") (pinfunction "1_1") (pintype "passive"))
      (node (ref "C11") (pin "1") (pinfunction "1_1") (pintype "passive"))
      (node (ref "C12") (pin "1") (pinfunction "1_1") (pintype "passive"))
      (node (ref "C13") (pin "1") (pinfunction "1_1") (pintype "passive"))
      (node (ref "C14") (pin "1") (pinfunction "1_1") (pintype "passive"))
      (node (ref "C15") (pin "1") (pinfunction "1_1") (pintype "passive"))
      (node (ref "C16") (pin "1") (pinfunction "1_1") (pintype "passive"))
      (node (ref "C17") (pin "1") (pinfunction "1_1") (pintype "passive"))
      (node (ref "C2") (pin "1") (pinfunction "1_1") (pintype "passive"))
      (node (ref "C3") (pin "1") (pinfunction "1_1") (pintype "passive"))
      (node (ref "C4") (pin "1") (pinfunction "1_1") (pintype "passive"))
      (node (ref "C5") (pin "1") (pinfunction "1_1") (pintype "passive"))
      (node (ref "C6") (pin "1") (pinfunction "1_1") (pintype "passive"))
      (node (ref "C7") (pin "1") (pinfunction "1_1") (pintype "passive"))
      (node (ref "C8") (pin "1") (pinfunction "1_1") (pintype "passive"))
      (node (ref "C9") (pin "1") (pinfunction "1_1") (pintype "passive"))
      (node (ref "D1") (pin "2") (pinfunction "2_2") (pintype "passive"))
      (node (ref "D2") (pin "2") (pinfunction "2_2") (pintype "passive"))
      (node (ref "D3") (pin "2") (pinfunction "2_2") (pintype "passive"))
      (node (ref "D4") (pin "1") (pinfunction "1_1") (pintype "passive"))
      (node (ref "D6") (pin "2") (pinfunction "2_2") (pintype "passive"))
      (node (ref "D7") (pin "2") (pinfunction "2_2") (pintype "passive"))
      (node (ref "D8") (pin "2") (pinfunction "2_2") (pintype "passive"))
      (node (ref "J1") (pin "1") (pinfunction "1_1") (pintype "passive"))
      (node (ref "J1") (pin "23") (pinfunction "23_23") (pintype "passive"))
      (node (ref "J2") (pin "2") (pinfunction "2_2") (pintype "passive"))
      (node (ref "J2") (pin "24") (pinfunction "24_24") (pintype "passive"))
      (node (ref "J3") (pin "A1B12") (pinfunction "GND_A1B12_A1B12") (pintype "passive"))
      (node (ref "J3") (pin "B1A12") (pinfunction "GND_B1A12_B1A12") (pintype "passive"))
      (node (ref "J3") (pin "S1") (pinfunction "SHIELD_1_S1") (pintype "passive"))
      (node (ref "J3") (pin "S2") (pinfunction "SHIELD_2_S2") (pintype "passive"))
      (node (ref "J3") (pin "S3") (pinfunction "SHIELD_3_S3") (pintype "passive"))
      (node (ref "J3") (pin "S4") (pinfunction "SHIELD_4_S4") (pintype "passive"))
      (node (ref "J4") (pin "A1B12") (pinfunction "GND_A1B12_A1B12") (pintype "passive"))
      (node (ref "J4") (pin "B1A12") (pinfunction "GND_B1A12_B1A12") (pintype "passive"))
      (node (ref "J4") (pin "S1") (pinfunction "SHIELD_1_S1") (pintype "passive"))
      (node (ref "J4") (pin "S2") (pinfunction "SHIELD_2_S2") (pintype "passive"))
      (node (ref "J4") (pin "S3") (pinfunction "SHIELD_3_S3") (pintype "passive"))
      (node (ref "J4") (pin "S4") (pinfunction "SHIELD_4_S4") (pintype "passive"))
      (node (ref "R10") (pin "1") (pinfunction "1_1") (pintype "passive"))
      (node (ref "R11") (pin "1") (pinfunction "1_1") (pintype "passive"))
      (node (ref "R12") (pin "1") (pinfunction "1_1") (pintype "passive"))
      (node (ref "R13") (pin "1") (pinfunction "1_1") (pintype "passive"))
      (node (ref "R14") (pin "1") (pinfunction "1_1") (pintype "passive"))
      (node (ref "R15") (pin "1") (pinfunction "1_1") (pintype "passive"))
      (node (ref "SW1") (pin "3") (pinfunction "3_3") (pintype "passive"))
      (node (ref "SW1") (pin "4") (pinfunction "4_4") (pintype "passive"))
      (node (ref "SW2") (pin "3") (pinfunction "3_3") (pintype "passive"))
      (node (ref "SW2") (pin "4") (pinfunction "4_4") (pintype "passive"))
      (node (ref "U1") (pin "1") (pinfunction "GND_1_1") (pintype "passive"))
      (node (ref "U1") (pin "2") (pinfunction "GND_2_2") (pintype "passive"))
      (node (ref "U1") (pin "42") (pinfunction "GND_42_42") (pintype "passive"))
      (node (ref "U1") (pin "43") (pinfunction "GND_43_43") (pintype "passive"))
      (node (ref "U1") (pin "46") (pinfunction "GND_46_46") (pintype "passive"))
      (node (ref "U1") (pin "47") (pinfunction "GND_47_47") (pintype "passive"))
      (node (ref "U1") (pin "48") (pinfunction "GND_48_48") (pintype "passive"))
      (node (ref "U1") (pin "49") (pinfunction "GND_49_49") (pintype "passive"))
      (node (ref "U1") (pin "50") (pinfunction "GND_50_50") (pintype "passive"))
      (node (ref "U1") (pin "51") (pinfunction "GND_51_51") (pintype "passive"))
      (node (ref "U1") (pin "52") (pinfunction "GND_52_52") (pintype "passive"))
      (node (ref "U1") (pin "53") (pinfunction "GND_53_53") (pintype "passive"))
      (node (ref "U1") (pin "54") (pinfunction "GND_54_54") (pintype "passive"))
      (node (ref "U1") (pin "55") (pinfunction "GND_55_55") (pintype "passive"))
      (node (ref "U1") (pin "56") (pinfunction "GND_56_56") (pintype "passive"))
      (node (ref "U1") (pin "57") (pinfunction "GND_57_57") (pintype "passive"))
      (node (ref "U1") (pin "58") (pinfunction "GND_58_58") (pintype "passive"))
      (node (ref "U1") (pin "59") (pinfunction "GND_59_59") (pintype "passive"))
      (node (ref "U1") (pin "60") (pinfunction "GND_60_60") (pintype "passive"))
      (node (ref "U1") (pin "61") (pinfunction "GND_61_61") (pintype "passive"))
      (node (ref "U1") (pin "62") (pinfunction "GND_62_62") (pintype "passive"))
      (node (ref "U1") (pin "63") (pinfunction "GND_63_63") (pintype "passive"))
      (node (ref "U1") (pin "64") (pinfunction "GND_64_64") (pintype "passive"))
      (node (ref "U1") (pin "65") (pinfunction "GND_65_65") (pintype "passive"))
      (node (ref "U1") (pin "66") (pinfunction "GND_66_66") (pintype "passive"))
      (node (ref "U1") (pin "67") (pinfunction "GND_67_67") (pintype "passive"))
      (node (ref "U1") (pin "68") (pinfunction "GND_68_68") (pintype "passive"))
      (node (ref "U1") (pin "69") (pinfunction "GND_69_69") (pintype "passive"))
      (node (ref "U1") (pin "70") (pinfunction "GND_70_70") (pintype "passive"))
      (node (ref "U1") (pin "71") (pinfunction "GND_71_71") (pintype "passive"))
      (node (ref "U1") (pin "72") (pinfunction "GND_72_72") (pintype "passive"))
      (node (ref "U1") (pin "73") (pinfunction "GND_73_73") (pintype "passive"))
      (node (ref "U2") (pin "13") (pinfunction "GND_13") (pintype "passive"))
      (node (ref "U2") (pin "21") (pinfunction "GND_21") (pintype "passive"))
      (node (ref "U2") (pin "3") (pinfunction "GND_3") (pintype "passive"))
      (node (ref "U3") (pin "2") (pinfunction "GND_2") (pintype "power_in"))
      (node (ref "U3") (pin "4") (pinfunction "GND_4") (pintype "power_in"))
    )
    (net (code "64") (name "Net-(D4-Pad2)") (class "Default")
      (node (ref "D4") (pin "2") (pinfunction "2_2") (pintype "passive"))
      (node (ref "R8") (pin "1") (pinfunction "1_1") (pintype "passive"))
    )
    (net (code "65") (name "Net-(D5-Pad2)") (class "Default")
      (node (ref "D5") (pin "2") (pinfunction "2_2") (pintype "passive"))
      (node (ref "R9") (pin "1") (pinfunction "1_1") (pintype "passive"))
    )
    (net (code "66") (name "Net-(J3-CC1)") (class "Default")
      (node (ref "J3") (pin "A5") (pinfunction "CC1_A5") (pintype "passive"))
      (node (ref "R12") (pin "2") (pinfunction "2_2") (pintype "passive"))
    )
    (net (code "67") (name "Net-(J3-CC2)") (class "Default")
      (node (ref "J3") (pin "B5") (pinfunction "CC2_B5") (pintype "passive"))
      (node (ref "R11") (pin "2") (pinfunction "2_2") (pintype "passive"))
    )
    (net (code "68") (name "Net-(J4-CC1)") (class "Default")
      (node (ref "J4") (pin "A5") (pinfunction "CC1_A5") (pintype "passive"))
      (node (ref "R15") (pin "2") (pinfunction "2_2") (pintype "passive"))
    )
    (net (code "69") (name "Net-(J4-CC2)") (class "Default")
      (node (ref "J4") (pin "B5") (pinfunction "CC2_B5") (pintype "passive"))
      (node (ref "R14") (pin "2") (pinfunction "2_2") (pintype "passive"))
    )
    (net (code "70") (name "Net-(Q1-B)") (class "Default")
      (node (ref "Q1") (pin "1") (pinfunction "B_1") (pintype "passive"))
      (node (ref "R20") (pin "1") (pinfunction "1_1") (pintype "passive"))
    )
    (net (code "71") (name "Net-(Q2-B)") (class "Default")
      (node (ref "Q2") (pin "1") (pinfunction "B_1") (pintype "passive"))
      (node (ref "R22") (pin "1") (pinfunction "1_1") (pintype "passive"))
    )
    (net (code "72") (name "Net-(U2-CBUS0)") (class "Default")
      (node (ref "R10") (pin "2") (pinfunction "2_2") (pintype "passive"))
      (node (ref "U2") (pin "15") (pinfunction "CBUS0_15") (pintype "passive"))
    )
    (net (code "73") (name "Net-(U2-~{RESET})") (class "Default")
      (node (ref "C7") (pin "2") (pinfunction "2_2") (pintype "passive"))
      (node (ref "R6") (pin "2") (pinfunction "2_2") (pintype "passive"))
      (node (ref "U2") (pin "11") (pinfunction "~{RESET}_11") (pintype "passive"))
    )
    (net (code "74") (name "unconnected-(J1-Pad24)") (class "Default")
      (node (ref "J1") (pin "24") (pinfunction "24_24") (pintype "passive+no_connect"))
    )
    (net (code "75") (name "unconnected-(J3-SBU1-PadA8)") (class "Default")
      (node (ref "J3") (pin "A8") (pinfunction "SBU1_A8") (pintype "passive+no_connect"))
    )
    (net (code "76") (name "unconnected-(J3-SBU2-PadB8)") (class "Default")
      (node (ref "J3") (pin "B8") (pinfunction "SBU2_B8") (pintype "passive+no_connect"))
    )
    (net (code "77") (name "unconnected-(J4-SBU1-PadA8)") (class "Default")
      (node (ref "J4") (pin "A8") (pinfunction "SBU1_A8") (pintype "passive+no_connect"))
    )
    (net (code "78") (name "unconnected-(J4-SBU2-PadB8)") (class "Default")
      (node (ref "J4") (pin "B8") (pinfunction "SBU2_B8") (pintype "passive+no_connect"))
    )
    (net (code "79") (name "unconnected-(U2-CBUS1-Pad14)") (class "Default")
      (node (ref "U2") (pin "14") (pinfunction "CBUS1_14") (pintype "passive+no_connect"))
    )
    (net (code "80") (name "unconnected-(U2-CBUS2-Pad7)") (class "Default")
      (node (ref "U2") (pin "7") (pinfunction "CBUS2_7") (pintype "passive+no_connect"))
    )
    (net (code "81") (name "unconnected-(U2-~{CTS}-Pad6)") (class "Default")
      (node (ref "U2") (pin "6") (pinfunction "~{CTS}_6") (pintype "passive+no_connect"))
    )
    (net (code "82") (name "unconnected-(U2-~{DCD}-Pad5)") (class "Default")
      (node (ref "U2") (pin "5") (pinfunction "~{DCD}_5") (pintype "passive+no_connect"))
    )
    (net (code "83") (name "unconnected-(U2-~{DSR}-Pad4)") (class "Default")
      (node (ref "U2") (pin "4") (pinfunction "~{DSR}_4") (pintype "passive+no_connect"))
    )
    (net (code "84") (name "unconnected-(U2-~{RI}-Pad2)") (class "Default")
      (node (ref "U2") (pin "2") (pinfunction "~{RI}_2") (pintype "passive+no_connect"))
    )
  )
)
